# design.net
KiCad netlist of a schematic drawn in Altium Designer
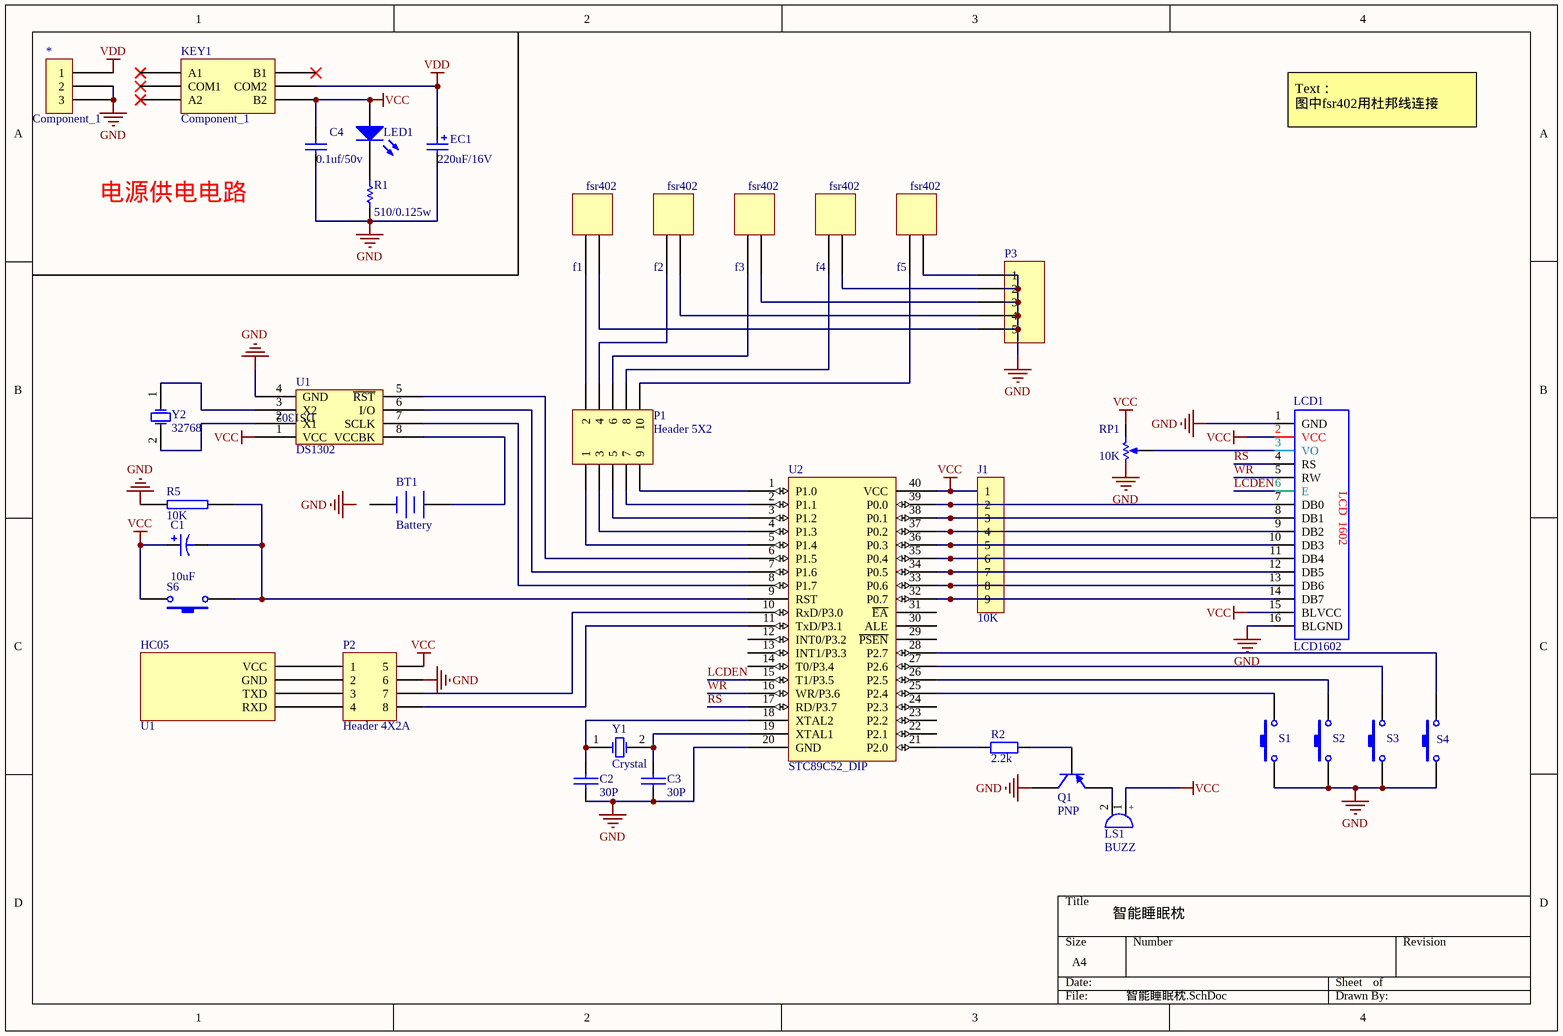
[diagram p0: 智能睡眠枕.SchDoc]

(export (version "E")
  (design (tool "Eeschema 10.0.6"))
  (components
    (comp (ref "*")
      (value "Component_1")
      (footprint "DC-0005电源插座封装:PCBComponent_1")
      (libsource (lib "DC电源") (part "Component_1"))
    )
    (comp (ref "BT1")
      (value "Battery")
      (footprint "BAT-2")
      (description "Multicell Battery")
      (fields (field (name "PUBLISHER") "Altium Limited"))
      (libsource (lib "Miscellaneous Devices") (part "Battery"))
    )
    (comp (ref "C1")
      (value "10uF")
      (footprint "C0805")
      (description "Polarized Capacitor (Surface Mount)")
      (fields (field (name "Comment") "Cap Pol3") (field (name "PUBLISHER") "Altium Limited"))
      (libsource (lib "Miscellaneous Devices") (part "Cap Pol3"))
    )
    (comp (ref "C2")
      (value "30P")
      (footprint "Capacitor-Disk-Small")
      (description "Capacitor")
      (libsource (lib "*") (part "CAP"))
    )
    (comp (ref "C3")
      (value "30P")
      (footprint "Capacitor-Disk-Small")
      (description "Capacitor")
      (libsource (lib "*") (part "CAP"))
    )
    (comp (ref "C4")
      (value "0.1uf/50v")
      (footprint "RAD-0.3")
      (description "Capacitor")
      (fields (field (name "Comment") "Cap") (field (name "PUBLISHER") "Altium Limited"))
      (libsource (lib "Miscellaneous Devices") (part "Cap"))
    )
    (comp (ref "EC1")
      (value "220uF/16V")
      (footprint "Capacitor-Disk-Middle")
      (description "Polarized Capacitor (Axial)")
      (fields (field (name "Comment") "Cap Pol2") (field (name "PUBLISHER") "Altium Limited"))
      (libsource (lib "Miscellaneous Devices") (part "Cap Pol2"))
    )
    (comp (ref "f1")
      (value "fsr402")
      (footprint "PCBComponent_1")
      (libsource (lib "压力传感器") (part "COMPONENT_1"))
    )
    (comp (ref "f2")
      (value "fsr402")
      (footprint "PCBComponent_1")
      (libsource (lib "压力传感器") (part "COMPONENT_1"))
    )
    (comp (ref "f3")
      (value "fsr402")
      (footprint "PCBComponent_1")
      (libsource (lib "压力传感器") (part "COMPONENT_1"))
    )
    (comp (ref "f4")
      (value "fsr402")
      (footprint "PCBComponent_1")
      (libsource (lib "压力传感器") (part "COMPONENT_1"))
    )
    (comp (ref "f5")
      (value "fsr402")
      (footprint "PCBComponent_1")
      (libsource (lib "压力传感器") (part "COMPONENT_1"))
    )
    (comp (ref "HC05") (value "U1") (footprint "HC-0x") (libsource (lib "蓝牙模块") (part "Component_1")))
    (comp (ref "J1")
      (value "10K")
      (footprint "RES-PACK-DIP9")
      (description "Connector")
      (libsource (lib "*") (part "CON9"))
    )
    (comp (ref "KEY1")
      (value "Component_1")
      (footprint "PCBComponent_1 - duplicate1")
      (libsource (lib "电源开关") (part "Component_1"))
    )
    (comp (ref "LCD1")
      (value "LCD1602")
      (footprint "LCD1602")
      (libsource (lib "03-EButterflyIntegratedLibrary") (part "LCD1602"))
    )
    (comp (ref "LED1")
      (value "LED Chip")
      (footprint "CLED1005-0402")
      (description "Typical Chip LED")
      (fields (field (name "PUBLISHER") "Altium Limited"))
      (libsource (lib "03-EButterflyIntegratedLibrary") (part "LED Chip"))
    )
    (comp (ref "LS1")
      (value "BUZZ")
      (footprint "BUZZER_12*9.5")
      (description "蜂鸣器")
      (libsource (lib "02 Miscellaneous_Devices_ZSF_Library") (part "BUZZ"))
    )
    (comp (ref "P1")
      (value "Header 5X2")
      (footprint "HDR2X5")
      (description "Header, 5-Pin, Dual row")
      (fields (field (name "PUBLISHER") "Altium Limited"))
      (libsource (lib "Miscellaneous Connectors") (part "Header 5X2"))
    )
    (comp (ref "P2")
      (value "Header 4X2A")
      (footprint "HDR2X4_CEN")
      (description "Header, 4-Pin, Dual row")
      (fields (field (name "PUBLISHER") "Altium Limited"))
      (libsource (lib "Miscellaneous Connectors") (part "Header 4X2A"))
    )
    (comp (ref "P3")
      (value "Header 5H")
      (footprint "HDR1X5H")
      (description "Header, 5-Pin, Right Angle")
      (fields (field (name "PUBLISHER") "Altium Limited"))
      (libsource (lib "Miscellaneous Connectors") (part "Header 5H"))
    )
    (comp (ref "Q1")
      (value "PNP")
      (footprint "SOT-23B_N")
      (description "PNP Bipolar Transistor")
      (fields (field (name "PUBLISHER") "Altium Limited"))
      (libsource (lib "Miscellaneous Devices") (part "PNP"))
    )
    (comp (ref "R1")
      (value "510/0.125w")
      (footprint "AXIAL-0.3")
      (description "Resistor")
      (fields (field (name "Comment") "Res1") (field (name "PUBLISHER") "Altium Limited"))
      (libsource (lib "Miscellaneous Devices") (part "Res1"))
    )
    (comp (ref "R2")
      (value "2.2k")
      (footprint "AXIAL-0.4-R")
      (description "Resistor 直插电阻 0.25W")
      (fields (field (name "PUBLISHER") "Altium Limited"))
      (libsource (lib "02 Miscellaneous_Devices_ZSF_Library") (part "Res2_1/4W"))
    )
    (comp (ref "R5") (value "10K") (footprint "AXIAL-0.3") (libsource (lib "*") (part "RES2")))
    (comp (ref "RP1")
      (value "10K")
      (footprint "VR5")
      (description "Potentiometer")
      (fields (field (name "Comment") "RPot") (field (name "PUBLISHER") "Altium Limited"))
      (libsource (lib "Miscellaneous Devices") (part "RPot"))
    )
    (comp (ref "S1")
      (value "Tactile Switch")
      (footprint "BUTTON_6*6")
      (description "Tactile Switch触觉开关")
      (fields (field (name "PUBLISHER") "Altium Limited"))
      (libsource (lib "02 Miscellaneous_Devices_ZSF_Library") (part "SW-PB"))
    )
    (comp (ref "S2")
      (value "Tactile Switch")
      (footprint "BUTTON_6*6")
      (description "Tactile Switch触觉开关")
      (fields (field (name "PUBLISHER") "Altium Limited"))
      (libsource (lib "02 Miscellaneous_Devices_ZSF_Library") (part "SW-PB"))
    )
    (comp (ref "S3")
      (value "Tactile Switch")
      (footprint "BUTTON_6*6")
      (description "Tactile Switch触觉开关")
      (fields (field (name "PUBLISHER") "Altium Limited"))
      (libsource (lib "02 Miscellaneous_Devices_ZSF_Library") (part "SW-PB"))
    )
    (comp (ref "S4")
      (value "Tactile Switch")
      (footprint "BUTTON_6*6")
      (description "Tactile Switch触觉开关")
      (fields (field (name "PUBLISHER") "Altium Limited"))
      (libsource (lib "02 Miscellaneous_Devices_ZSF_Library") (part "SW-PB"))
    )
    (comp (ref "S6")
      (value "Tactile Switch")
      (footprint "BUTTON_6*6")
      (description "Tactile Switch触觉开关")
      (fields (field (name "PUBLISHER") "Altium Limited"))
      (libsource (lib "02 Miscellaneous_Devices_ZSF_Library") (part "SW-PB"))
    )
    (comp (ref "U1")
      (value "DS1302")
      (footprint "DIP-8")
      (description "Clock")
      (libsource (lib "03-EButterflyIntegratedLibrary") (part "DS1302"))
    )
    (comp (ref "U2")
      (value "STC89C52_DIP")
      (footprint "DIP-40")
      (libsource (lib "02 Miscellaneous_Devices_ZSF_Library") (part "STC89C52_DIP"))
    )
    (comp (ref "Y1")
      (value "Crystal")
      (footprint "cry卧式")
      (description "直插晶振11.05292/12/16/24/MHz")
      (libsource (lib "02 Miscellaneous_Devices_ZSF_Library") (part "Crystal 11.05292/12/16/24/MHz"))
    )
    (comp (ref "Y2")
      (value "32768")
      (footprint "cry卧式")
      (description "柱状晶振32.768kHz")
      (libsource (lib "02 Miscellaneous_Devices_ZSF_Library") (part "Crystal 11.05292/12/16/24/MHz_1"))
    )
  )
  (nets
    (net (code "1") (name "/LCDEN") (class "Default")
      (node (ref "LCD1") (pin "6") (pinfunction "E_6") (pintype "passive"))
      (node (ref "U2") (pin "15") (pinfunction "T1/P3.5_15") (pintype "bidirectional"))
    )
    (net (code "2") (name "/RS") (class "Default")
      (node (ref "LCD1") (pin "4") (pinfunction "RS_4") (pintype "passive"))
      (node (ref "U2") (pin "17") (pinfunction "RD/P3.7_17") (pintype "bidirectional"))
    )
    (net (code "3") (name "/WR") (class "Default")
      (node (ref "LCD1") (pin "5") (pinfunction "RW_5") (pintype "passive"))
      (node (ref "U2") (pin "16") (pinfunction "WR/P3.6_16") (pintype "bidirectional"))
    )
    (net (code "4") (name "GND") (class "Default")
      (node (ref "*") (pin "2") (pinfunction "2_2") (pintype "passive"))
      (node (ref "*") (pin "3") (pinfunction "3_3") (pintype "passive"))
      (node (ref "C2") (pin "1") (pinfunction "1_1") (pintype "passive"))
      (node (ref "C3") (pin "1") (pinfunction "1_1") (pintype "passive"))
      (node (ref "C4") (pin "1") (pinfunction "1_1") (pintype "passive"))
      (node (ref "EC1") (pin "2") (pinfunction "2_2") (pintype "passive"))
      (node (ref "LCD1") (pin "1") (pinfunction "GND_1") (pintype "passive"))
      (node (ref "LCD1") (pin "16") (pinfunction "BLGND_16") (pintype "passive"))
      (node (ref "P2") (pin "6") (pinfunction "6_6") (pintype "passive"))
      (node (ref "Q1") (pin "1") (pinfunction "C_1") (pintype "passive"))
      (node (ref "R1") (pin "1") (pinfunction "1_1") (pintype "passive"))
      (node (ref "R5") (pin "1") (pinfunction "1_1") (pintype "passive"))
      (node (ref "S1") (pin "2") (pinfunction "2_2") (pintype "passive"))
      (node (ref "S2") (pin "2") (pinfunction "2_2") (pintype "passive"))
      (node (ref "S3") (pin "2") (pinfunction "2_2") (pintype "passive"))
      (node (ref "S4") (pin "2") (pinfunction "2_2") (pintype "passive"))
      (node (ref "U1") (pin "4") (pinfunction "GND_4") (pintype "passive"))
      (node (ref "U2") (pin "20") (pinfunction "GND_20") (pintype "power_in"))
    )
    (net (code "5") (name "Net-(BT1-+)") (class "Default")
      (node (ref "BT1") (pin "1") (pinfunction "+_1") (pintype "passive"))
      (node (ref "U1") (pin "8") (pinfunction "VCCBK_8") (pintype "passive"))
    )
    (net (code "6") (name "Net-(HC05-GND)") (class "Default")
      (node (ref "HC05") (pin "18") (pinfunction "GND_18") (pintype "passive"))
      (node (ref "P2") (pin "2") (pinfunction "2_2") (pintype "passive"))
    )
    (net (code "7") (name "Net-(HC05-RXD)") (class "Default")
      (node (ref "HC05") (pin "16") (pinfunction "RXD_16") (pintype "passive"))
      (node (ref "P2") (pin "4") (pinfunction "4_4") (pintype "passive"))
    )
    (net (code "8") (name "Net-(HC05-TXD)") (class "Default")
      (node (ref "HC05") (pin "17") (pinfunction "TXD_17") (pintype "passive"))
      (node (ref "P2") (pin "3") (pinfunction "3_3") (pintype "passive"))
    )
    (net (code "9") (name "Net-(HC05-VCC)") (class "Default")
      (node (ref "HC05") (pin "19") (pinfunction "VCC_19") (pintype "passive"))
      (node (ref "P2") (pin "1") (pinfunction "1_1") (pintype "passive"))
    )
    (net (code "10") (name "Net-(LCD1-DB0)") (class "Default")
      (node (ref "J1") (pin "2") (pinfunction "2_2") (pintype "passive"))
      (node (ref "LCD1") (pin "7") (pinfunction "DB0_7") (pintype "passive"))
      (node (ref "U2") (pin "39") (pinfunction "P0.0_39") (pintype "bidirectional"))
    )
    (net (code "11") (name "Net-(LCD1-DB1)") (class "Default")
      (node (ref "J1") (pin "3") (pinfunction "3_3") (pintype "passive"))
      (node (ref "LCD1") (pin "8") (pinfunction "DB1_8") (pintype "passive"))
      (node (ref "U2") (pin "38") (pinfunction "P0.1_38") (pintype "bidirectional"))
    )
    (net (code "12") (name "Net-(LCD1-DB2)") (class "Default")
      (node (ref "J1") (pin "4") (pinfunction "4_4") (pintype "passive"))
      (node (ref "LCD1") (pin "9") (pinfunction "DB2_9") (pintype "passive"))
      (node (ref "U2") (pin "37") (pinfunction "P0.2_37") (pintype "bidirectional"))
    )
    (net (code "13") (name "Net-(LCD1-DB3)") (class "Default")
      (node (ref "J1") (pin "5") (pinfunction "5_5") (pintype "passive"))
      (node (ref "LCD1") (pin "10") (pinfunction "DB3_10") (pintype "passive"))
      (node (ref "U2") (pin "36") (pinfunction "P0.3_36") (pintype "bidirectional"))
    )
    (net (code "14") (name "Net-(LCD1-DB4)") (class "Default")
      (node (ref "J1") (pin "6") (pinfunction "6_6") (pintype "passive"))
      (node (ref "LCD1") (pin "11") (pinfunction "DB4_11") (pintype "passive"))
      (node (ref "U2") (pin "35") (pinfunction "P0.4_35") (pintype "bidirectional"))
    )
    (net (code "15") (name "Net-(LCD1-DB5)") (class "Default")
      (node (ref "J1") (pin "7") (pinfunction "7_7") (pintype "passive"))
      (node (ref "LCD1") (pin "12") (pinfunction "DB5_12") (pintype "passive"))
      (node (ref "U2") (pin "34") (pinfunction "P0.5_34") (pintype "bidirectional"))
    )
    (net (code "16") (name "Net-(LCD1-DB6)") (class "Default")
      (node (ref "J1") (pin "8") (pinfunction "8_8") (pintype "passive"))
      (node (ref "LCD1") (pin "13") (pinfunction "DB6_13") (pintype "passive"))
      (node (ref "U2") (pin "33") (pinfunction "P0.6_33") (pintype "bidirectional"))
    )
    (net (code "17") (name "Net-(LCD1-DB7)") (class "Default")
      (node (ref "J1") (pin "9") (pinfunction "9_9") (pintype "passive"))
      (node (ref "LCD1") (pin "14") (pinfunction "DB7_14") (pintype "passive"))
      (node (ref "U2") (pin "32") (pinfunction "P0.7_32") (pintype "bidirectional"))
    )
    (net (code "18") (name "Net-(LCD1-VO)") (class "Default")
      (node (ref "LCD1") (pin "3") (pinfunction "VO_3") (pintype "passive"))
      (node (ref "RP1") (pin "3") (pinfunction "TAP_3") (pintype "passive"))
    )
    (net (code "19") (name "Net-(LED1-K)") (class "Default")
      (node (ref "LED1") (pin "2") (pinfunction "K_2") (pintype "passive"))
      (node (ref "R1") (pin "2") (pinfunction "2_2") (pintype "passive"))
    )
    (net (code "20") (name "Net-(Q1-B)") (class "Default")
      (node (ref "Q1") (pin "2") (pinfunction "B_2") (pintype "passive"))
      (node (ref "R2") (pin "1") (pinfunction "1_1") (pintype "passive"))
    )
    (net (code "21") (name "Net-(Q1-E)") (class "Default")
      (node (ref "LS1") (pin "2") (pinfunction "2_2") (pintype "passive"))
      (node (ref "Q1") (pin "3") (pinfunction "E_3") (pintype "passive"))
    )
    (net (code "22") (name "Net-(U1-I{slash}O)") (class "Default")
      (node (ref "U1") (pin "6") (pinfunction "I/O_6") (pintype "passive"))
      (node (ref "U2") (pin "7") (pinfunction "P1.6_7") (pintype "bidirectional"))
    )
    (net (code "23") (name "Net-(U1-SCLK)") (class "Default")
      (node (ref "U1") (pin "7") (pinfunction "SCLK_7") (pintype "passive"))
      (node (ref "U2") (pin "8") (pinfunction "P1.7_8") (pintype "bidirectional"))
    )
    (net (code "24") (name "Net-(U1-X1)") (class "Default")
      (node (ref "U1") (pin "2") (pinfunction "X1_2") (pintype "passive"))
      (node (ref "Y2") (pin "2") (pinfunction "OSC2_2") (pintype "passive"))
    )
    (net (code "25") (name "Net-(U1-X2)") (class "Default")
      (node (ref "U1") (pin "3") (pinfunction "X2_3") (pintype "passive"))
      (node (ref "Y2") (pin "1") (pinfunction "OSC1_1") (pintype "passive"))
    )
    (net (code "26") (name "Net-(U1-~{RST})") (class "Default")
      (node (ref "U1") (pin "5") (pinfunction "~{RST}_5") (pintype "passive"))
      (node (ref "U2") (pin "6") (pinfunction "P1.5_6") (pintype "bidirectional"))
    )
    (net (code "27") (name "Net-(U2-P1.0)") (class "Default")
      (node (ref "P1") (pin "9") (pinfunction "9_9") (pintype "passive"))
      (node (ref "U2") (pin "1") (pinfunction "P1.0_1") (pintype "bidirectional"))
    )
    (net (code "28") (name "Net-(U2-P1.1)") (class "Default")
      (node (ref "P1") (pin "7") (pinfunction "7_7") (pintype "passive"))
      (node (ref "U2") (pin "2") (pinfunction "P1.1_2") (pintype "bidirectional"))
    )
    (net (code "29") (name "Net-(U2-P1.2)") (class "Default")
      (node (ref "P1") (pin "5") (pinfunction "5_5") (pintype "passive"))
      (node (ref "U2") (pin "3") (pinfunction "P1.2_3") (pintype "bidirectional"))
    )
    (net (code "30") (name "Net-(U2-P1.3)") (class "Default")
      (node (ref "P1") (pin "3") (pinfunction "3_3") (pintype "passive"))
      (node (ref "U2") (pin "4") (pinfunction "P1.3_4") (pintype "bidirectional"))
    )
    (net (code "31") (name "Net-(U2-P1.4)") (class "Default")
      (node (ref "P1") (pin "1") (pinfunction "1_1") (pintype "passive"))
      (node (ref "U2") (pin "5") (pinfunction "P1.4_5") (pintype "bidirectional"))
    )
    (net (code "32") (name "Net-(U2-P2.0)") (class "Default")
      (node (ref "R2") (pin "2") (pinfunction "2_2") (pintype "passive"))
      (node (ref "U2") (pin "21") (pinfunction "P2.0_21") (pintype "bidirectional"))
    )
    (net (code "33") (name "Net-(U2-P2.4)") (class "Default")
      (node (ref "S1") (pin "1") (pinfunction "1_1") (pintype "passive"))
      (node (ref "U2") (pin "25") (pinfunction "P2.4_25") (pintype "bidirectional"))
    )
    (net (code "34") (name "Net-(U2-P2.5)") (class "Default")
      (node (ref "S2") (pin "1") (pinfunction "1_1") (pintype "passive"))
      (node (ref "U2") (pin "26") (pinfunction "P2.5_26") (pintype "bidirectional"))
    )
    (net (code "35") (name "Net-(U2-P2.6)") (class "Default")
      (node (ref "S3") (pin "1") (pinfunction "1_1") (pintype "passive"))
      (node (ref "U2") (pin "27") (pinfunction "P2.6_27") (pintype "bidirectional"))
    )
    (net (code "36") (name "Net-(U2-P2.7)") (class "Default")
      (node (ref "S4") (pin "1") (pinfunction "1_1") (pintype "passive"))
      (node (ref "U2") (pin "28") (pinfunction "P2.7_28") (pintype "bidirectional"))
    )
    (net (code "37") (name "Net-(U2-RST)") (class "Default")
      (node (ref "C1") (pin "2") (pinfunction "2_2") (pintype "passive"))
      (node (ref "R5") (pin "2") (pinfunction "2_2") (pintype "passive"))
      (node (ref "S6") (pin "2") (pinfunction "2_2") (pintype "passive"))
      (node (ref "U2") (pin "9") (pinfunction "RST_9") (pintype "passive"))
    )
    (net (code "38") (name "Net-(U2-RxD{slash}P3.0)") (class "Default")
      (node (ref "P2") (pin "7") (pinfunction "7_7") (pintype "passive"))
      (node (ref "U2") (pin "10") (pinfunction "RxD/P3.0_10") (pintype "bidirectional"))
    )
    (net (code "39") (name "Net-(U2-TxD{slash}P3.1)") (class "Default")
      (node (ref "P2") (pin "8") (pinfunction "8_8") (pintype "passive"))
      (node (ref "U2") (pin "11") (pinfunction "TxD/P3.1_11") (pintype "bidirectional"))
    )
    (net (code "40") (name "Net-(U2-XTAL1)") (class "Default")
      (node (ref "C3") (pin "2") (pinfunction "2_2") (pintype "passive"))
      (node (ref "U2") (pin "19") (pinfunction "XTAL1_19") (pintype "passive"))
      (node (ref "Y1") (pin "2") (pinfunction "OSC2_2") (pintype "passive"))
    )
    (net (code "41") (name "Net-(U2-XTAL2)") (class "Default")
      (node (ref "C2") (pin "2") (pinfunction "2_2") (pintype "passive"))
      (node (ref "U2") (pin "18") (pinfunction "XTAL2_18") (pintype "passive"))
      (node (ref "Y1") (pin "1") (pinfunction "OSC1_1") (pintype "passive"))
    )
    (net (code "42") (name "VCC") (class "Default")
      (node (ref "C1") (pin "1") (pinfunction "1_1") (pintype "passive"))
      (node (ref "C4") (pin "2") (pinfunction "2_2") (pintype "passive"))
      (node (ref "J1") (pin "1") (pinfunction "1_1") (pintype "passive"))
      (node (ref "KEY1") (pin "6") (pinfunction "B2_6") (pintype "passive"))
      (node (ref "LCD1") (pin "15") (pinfunction "BLVCC_15") (pintype "passive"))
      (node (ref "LCD1") (pin "2") (pinfunction "VCC_2") (pintype "passive"))
      (node (ref "LED1") (pin "1") (pinfunction "A_1") (pintype "passive"))
      (node (ref "LS1") (pin "1") (pinfunction "1_1") (pintype "passive"))
      (node (ref "P2") (pin "5") (pinfunction "5_5") (pintype "passive"))
      (node (ref "RP1") (pin "1") (pinfunction "TOP_1") (pintype "passive"))
      (node (ref "S6") (pin "1") (pinfunction "1_1") (pintype "passive"))
      (node (ref "U1") (pin "1") (pinfunction "VCC_1") (pintype "passive"))
      (node (ref "U2") (pin "40") (pinfunction "VCC_40") (pintype "power_in"))
    )
    (net (code "43") (name "VDD") (class "Default")
      (node (ref "*") (pin "1") (pinfunction "1_1") (pintype "passive"))
      (node (ref "EC1") (pin "1") (pinfunction "1_1") (pintype "passive"))
      (node (ref "KEY1") (pin "5") (pinfunction "COM2_5") (pintype "passive"))
    )
    (net (code "44") (name "unconnected-(BT1---Pad2)") (class "Default")
      (node (ref "BT1") (pin "2") (pinfunction "-_2") (pintype "passive"))
    )
    (net (code "45") (name "unconnected-(KEY1-A1-Pad1)") (class "Default")
      (node (ref "KEY1") (pin "1") (pinfunction "A1_1") (pintype "passive+no_connect"))
    )
    (net (code "46") (name "unconnected-(KEY1-A2-Pad3)") (class "Default")
      (node (ref "KEY1") (pin "3") (pinfunction "A2_3") (pintype "passive+no_connect"))
    )
    (net (code "47") (name "unconnected-(KEY1-B1-Pad4)") (class "Default")
      (node (ref "KEY1") (pin "4") (pinfunction "B1_4") (pintype "passive+no_connect"))
    )
    (net (code "48") (name "unconnected-(KEY1-COM1-Pad2)") (class "Default")
      (node (ref "KEY1") (pin "2") (pinfunction "COM1_2") (pintype "passive+no_connect"))
    )
    (net (code "49") (name "unconnected-(P1-Pad2)") (class "Default")
      (node (ref "P1") (pin "2") (pinfunction "2_2") (pintype "passive"))
    )
    (net (code "50") (name "unconnected-(P1-Pad4)") (class "Default")
      (node (ref "P1") (pin "4") (pinfunction "4_4") (pintype "passive"))
    )
    (net (code "51") (name "unconnected-(P1-Pad6)") (class "Default")
      (node (ref "P1") (pin "6") (pinfunction "6_6") (pintype "passive"))
    )
    (net (code "52") (name "unconnected-(P1-Pad8)") (class "Default")
      (node (ref "P1") (pin "8") (pinfunction "8_8") (pintype "passive"))
    )
    (net (code "53") (name "unconnected-(P1-Pad10)") (class "Default")
      (node (ref "P1") (pin "10") (pinfunction "10_10") (pintype "passive"))
    )
    (net (code "54") (name "unconnected-(P3-Pad1)") (class "Default")
      (node (ref "P3") (pin "1") (pinfunction "1_1") (pintype "passive"))
    )
    (net (code "55") (name "unconnected-(P3-Pad2)") (class "Default")
      (node (ref "P3") (pin "2") (pinfunction "2_2") (pintype "passive"))
    )
    (net (code "56") (name "unconnected-(P3-Pad3)") (class "Default")
      (node (ref "P3") (pin "3") (pinfunction "3_3") (pintype "passive"))
    )
    (net (code "57") (name "unconnected-(P3-Pad4)") (class "Default")
      (node (ref "P3") (pin "4") (pinfunction "4_4") (pintype "passive"))
    )
    (net (code "58") (name "unconnected-(P3-Pad5)") (class "Default")
      (node (ref "P3") (pin "5") (pinfunction "5_5") (pintype "passive"))
    )
    (net (code "59") (name "unconnected-(RP1-BOT-Pad2)") (class "Default")
      (node (ref "RP1") (pin "2") (pinfunction "BOT_2") (pintype "passive"))
    )
    (net (code "60") (name "unconnected-(U2-ALE-Pad30)") (class "Default")
      (node (ref "U2") (pin "30") (pinfunction "ALE_30") (pintype "passive"))
    )
    (net (code "61") (name "unconnected-(U2-INT0{slash}P3.2-Pad12)") (class "Default")
      (node (ref "U2") (pin "12") (pinfunction "INT0/P3.2_12") (pintype "bidirectional"))
    )
    (net (code "62") (name "unconnected-(U2-INT1{slash}P3.3-Pad13)") (class "Default")
      (node (ref "U2") (pin "13") (pinfunction "INT1/P3.3_13") (pintype "bidirectional"))
    )
    (net (code "63") (name "unconnected-(U2-P2.1-Pad22)") (class "Default")
      (node (ref "U2") (pin "22") (pinfunction "P2.1_22") (pintype "bidirectional"))
    )
    (net (code "64") (name "unconnected-(U2-P2.2-Pad23)") (class "Default")
      (node (ref "U2") (pin "23") (pinfunction "P2.2_23") (pintype "bidirectional"))
    )
    (net (code "65") (name "unconnected-(U2-P2.3-Pad24)") (class "Default")
      (node (ref "U2") (pin "24") (pinfunction "P2.3_24") (pintype "bidirectional"))
    )
    (net (code "66") (name "unconnected-(U2-T0{slash}P3.4-Pad14)") (class "Default")
      (node (ref "U2") (pin "14") (pinfunction "T0/P3.4_14") (pintype "bidirectional"))
    )
    (net (code "67") (name "unconnected-(U2-~{EA}-Pad31)") (class "Default")
      (node (ref "U2") (pin "31") (pinfunction "~{EA}_31") (pintype "passive"))
    )
    (net (code "68") (name "unconnected-(U2-~{PSEN}-Pad29)") (class "Default")
      (node (ref "U2") (pin "29") (pinfunction "~{PSEN}_29") (pintype "passive"))
    )
    (net (code "69") (name "unconnected-(f1-Pad0)") (class "Default")
      (node (ref "f1") (pin "0") (pinfunction "0_0") (pintype "passive"))
    )
    (net (code "70") (name "unconnected-(f1-Pad1)") (class "Default")
      (node (ref "f1") (pin "1") (pinfunction "1_1") (pintype "passive"))
    )
    (net (code "71") (name "unconnected-(f2-Pad0)") (class "Default")
      (node (ref "f2") (pin "0") (pinfunction "0_0") (pintype "passive"))
    )
    (net (code "72") (name "unconnected-(f2-Pad1)") (class "Default")
      (node (ref "f2") (pin "1") (pinfunction "1_1") (pintype "passive"))
    )
    (net (code "73") (name "unconnected-(f3-Pad0)") (class "Default")
      (node (ref "f3") (pin "0") (pinfunction "0_0") (pintype "passive"))
    )
    (net (code "74") (name "unconnected-(f3-Pad1)") (class "Default")
      (node (ref "f3") (pin "1") (pinfunction "1_1") (pintype "passive"))
    )
    (net (code "75") (name "unconnected-(f4-Pad0)") (class "Default")
      (node (ref "f4") (pin "0") (pinfunction "0_0") (pintype "passive"))
    )
    (net (code "76") (name "unconnected-(f4-Pad1)") (class "Default")
      (node (ref "f4") (pin "1") (pinfunction "1_1") (pintype "passive"))
    )
    (net (code "77") (name "unconnected-(f5-Pad0)") (class "Default")
      (node (ref "f5") (pin "0") (pinfunction "0_0") (pintype "passive"))
    )
    (net (code "78") (name "unconnected-(f5-Pad1)") (class "Default")
      (node (ref "f5") (pin "1") (pinfunction "1_1") (pintype "passive"))
    )
  )
)
